# Ethernet.net
KiCad netlist of a schematic drawn in Altium Designer
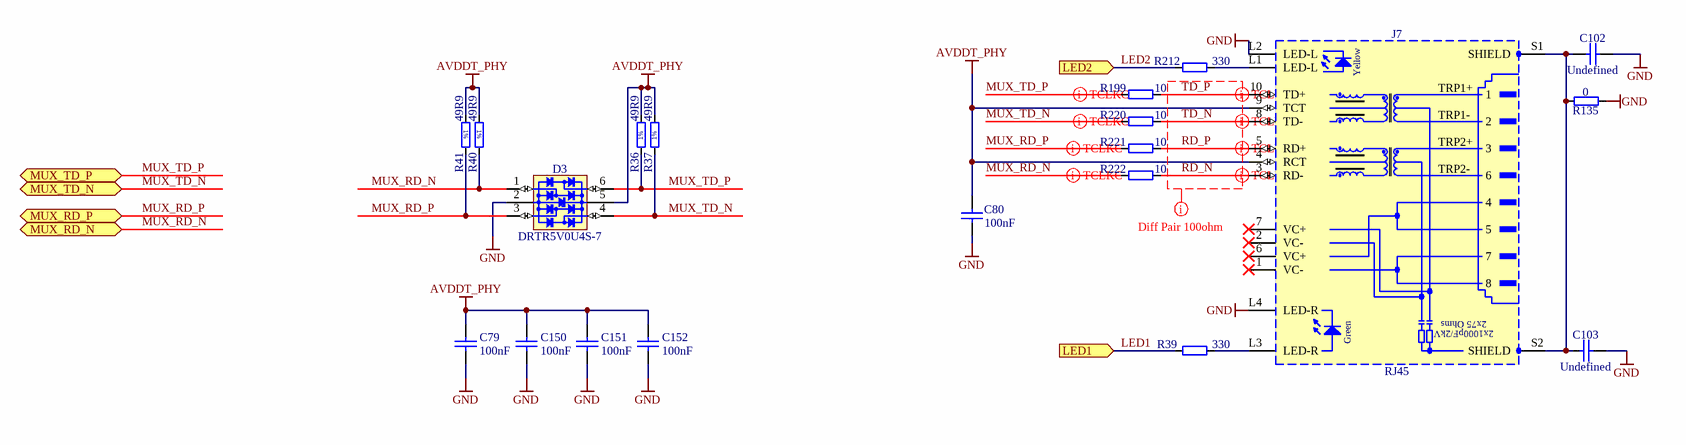
[diagram p0: Ethernet.SchDoc]

(export (version "E")
  (design (tool "Eeschema 10.0.6"))
  (components
    (comp (ref "C79")
      (value "100nF")
      (footprint "CAPC1005X55N")
      (description "Non-polarised capacitor")
      (fields
        (field (name "PART NUMBER") "CC0402_100NF_16V_10%_X5R")
        (field (name "VOLTAGE") "16V")
        (field (name "AUTHOR") "CERN DEM JLC")
      )
      (libsource (lib "Capacitors") (part "Capacitor - non polarized"))
    )
    (comp (ref "C80")
      (value "100nF")
      (footprint "CAPC1005X55N")
      (description "Non-polarised capacitor")
      (fields
        (field (name "PART NUMBER") "CC0402_100NF_16V_10%_X5R")
        (field (name "VOLTAGE") "16V")
        (field (name "AUTHOR") "CERN DEM JLC")
      )
      (libsource (lib "Capacitors") (part "Capacitor - non polarized"))
    )
    (comp (ref "C102")
      (value "Undefined")
      (footprint "CAPC2012X135N")
      (description "Non-polarised capacitor")
      (fields (field (name "PART NUMBER") "CC0805_NO-VALUE") (field (name "AUTHOR") "CERN DEM JLC"))
      (libsource (lib "Capacitors") (part "Capacitor - non polarized"))
    )
    (comp (ref "C103")
      (value "Undefined")
      (footprint "CAPC2012X135N")
      (description "Non-polarised capacitor")
      (fields (field (name "PART NUMBER") "CC0805_NO-VALUE") (field (name "AUTHOR") "CERN DEM JLC"))
      (libsource (lib "Capacitors") (part "Capacitor - non polarized"))
    )
    (comp (ref "C150")
      (value "100nF")
      (footprint "CAPC1005X55N")
      (description "Non-polarised capacitor")
      (fields
        (field (name "PART NUMBER") "CC0402_100NF_16V_10%_X5R")
        (field (name "VOLTAGE") "16V")
        (field (name "AUTHOR") "CERN DEM JLC")
      )
      (libsource (lib "Capacitors") (part "Capacitor - non polarized"))
    )
    (comp (ref "C151")
      (value "100nF")
      (footprint "CAPC1005X55N")
      (description "Non-polarised capacitor")
      (fields
        (field (name "PART NUMBER") "CC0402_100NF_16V_10%_X5R")
        (field (name "VOLTAGE") "16V")
        (field (name "AUTHOR") "CERN DEM JLC")
      )
      (libsource (lib "Capacitors") (part "Capacitor - non polarized"))
    )
    (comp (ref "C152")
      (value "100nF")
      (footprint "CAPC1005X55N")
      (description "Non-polarised capacitor")
      (fields
        (field (name "PART NUMBER") "CC0402_100NF_16V_10%_X5R")
        (field (name "VOLTAGE") "16V")
        (field (name "AUTHOR") "CERN DEM JLC")
      )
      (libsource (lib "Capacitors") (part "Capacitor - non polarized"))
    )
    (comp (ref "D3")
      (value "DRTR5V0U4S-7")
      (footprint "SOT65P210X110-6N")
      (description "Integrated Quad Ultra-Low Capacitance ESD Protection")
      (fields (field (name "MANUFACTURER") "DIODES") (field (name "AUTHOR") "GK"))
      (libsource (lib "Diodes") (part "D_TVS_DRTR5V0U4S-7"))
    )
    (comp (ref "J7")
      (value "RJ45")
      (footprint "ABRACON_ARJM11C7-114-BA-EW2")
      (description "MagJack 10/100BaseT, PoE+, 1X1, OG/Y, -40 to 85*C, Tab Up, RoHS")
      (fields
        (field (name "PART NUMBER") "ARJM11C7-114-BA-EW2")
        (field (name "MANUFACTURER") "Abracon")
        (field (name "AUTHOR") "GK")
      )
      (libsource (lib "LIBRARY_SCH") (part "CON_ETH_POE_ARJM11C7"))
    )
    (comp (ref "R36")
      (value "49R9")
      (footprint "RESC1005X40N")
      (description "Resistor - 1%")
      (fields
        (field (name "PART NUMBER") "R0402_49R9_1%_0.0625W_100PPM")
        (field (name "POWER") "0.0625W")
        (field (name "AUTHOR") "CERN DEM JLC")
      )
      (libsource (lib "Resistors") (part "Resistor - 1%"))
    )
    (comp (ref "R37")
      (value "49R9")
      (footprint "RESC1005X40N")
      (description "Resistor - 1%")
      (fields
        (field (name "PART NUMBER") "R0402_49R9_1%_0.0625W_100PPM")
        (field (name "POWER") "0.0625W")
        (field (name "AUTHOR") "CERN DEM JLC")
      )
      (libsource (lib "Resistors") (part "Resistor - 1%"))
    )
    (comp (ref "R39")
      (value "330")
      (footprint "RESC1005X40N")
      (description "Resistor - 1%")
      (fields
        (field (name "PART NUMBER") "R0402_330R_1%_0.0625W_100PPM")
        (field (name "POWER") "0.0625W")
        (field (name "AUTHOR") "CERN DEM JLC")
      )
      (libsource (lib "Resistors") (part "Resistor - 1%"))
    )
    (comp (ref "R40")
      (value "49R9")
      (footprint "RESC1005X40N")
      (description "Resistor - 1%")
      (fields
        (field (name "PART NUMBER") "R0402_49R9_1%_0.0625W_100PPM")
        (field (name "POWER") "0.0625W")
        (field (name "AUTHOR") "CERN DEM JLC")
      )
      (libsource (lib "Resistors") (part "Resistor - 1%"))
    )
    (comp (ref "R41")
      (value "49R9")
      (footprint "RESC1005X40N")
      (description "Resistor - 1%")
      (fields
        (field (name "PART NUMBER") "R0402_49R9_1%_0.0625W_100PPM")
        (field (name "POWER") "0.0625W")
        (field (name "AUTHOR") "CERN DEM JLC")
      )
      (libsource (lib "Resistors") (part "Resistor - 1%"))
    )
    (comp (ref "R135")
      (value "0")
      (footprint "RESC1608X55N")
      (description "Resistor")
      (fields
        (field (name "PART NUMBER") "R0603_0R_JUMPER")
        (field (name "MANUFACTURER") "GENERIC")
        (field (name "AUTHOR") "CERN DEM JLC")
      )
      (libsource (lib "Resistors") (part "Resistor"))
    )
    (comp (ref "R199")
      (value "10")
      (footprint "RESC1005X40N")
      (description "Resistor - 1%")
      (fields
        (field (name "PART NUMBER") "R0402_10R_1%_0.0625W_200PPM")
        (field (name "POWER") "0.0625W")
        (field (name "AUTHOR") "CERN DEM JLC")
      )
      (libsource (lib "Resistors") (part "Resistor - 1%"))
    )
    (comp (ref "R212")
      (value "330")
      (footprint "RESC1005X40N")
      (description "Resistor - 1%")
      (fields
        (field (name "PART NUMBER") "R0402_330R_1%_0.0625W_100PPM")
        (field (name "POWER") "0.0625W")
        (field (name "AUTHOR") "CERN DEM JLC")
      )
      (libsource (lib "Resistors") (part "Resistor - 1%"))
    )
    (comp (ref "R220")
      (value "10")
      (footprint "RESC1005X40N")
      (description "Resistor - 1%")
      (fields
        (field (name "PART NUMBER") "R0402_10R_1%_0.0625W_200PPM")
        (field (name "POWER") "0.0625W")
        (field (name "AUTHOR") "CERN DEM JLC")
      )
      (libsource (lib "Resistors") (part "Resistor - 1%"))
    )
    (comp (ref "R221")
      (value "10")
      (footprint "RESC1005X40N")
      (description "Resistor - 1%")
      (fields
        (field (name "PART NUMBER") "R0402_10R_1%_0.0625W_200PPM")
        (field (name "POWER") "0.0625W")
        (field (name "AUTHOR") "CERN DEM JLC")
      )
      (libsource (lib "Resistors") (part "Resistor - 1%"))
    )
    (comp (ref "R222")
      (value "10")
      (footprint "RESC1005X40N")
      (description "Resistor - 1%")
      (fields
        (field (name "PART NUMBER") "R0402_10R_1%_0.0625W_200PPM")
        (field (name "POWER") "0.0625W")
        (field (name "AUTHOR") "CERN DEM JLC")
      )
      (libsource (lib "Resistors") (part "Resistor - 1%"))
    )
  )
  (nets
    (net (code "1") (name "/LED1") (class "Default")
      (node (ref "R39") (pin "1") (pinfunction "1_1") (pintype "passive"))
    )
    (net (code "2") (name "/LED2") (class "Default")
      (node (ref "R212") (pin "1") (pinfunction "1_1") (pintype "passive"))
    )
    (net (code "3") (name "/MUX_RD_N") (class "Default")
      (node (ref "D3") (pin "1") (pinfunction "I/O1_1") (pintype "bidirectional"))
      (node (ref "R222") (pin "1") (pinfunction "1_1") (pintype "passive"))
      (node (ref "R40") (pin "2") (pinfunction "2_2") (pintype "passive"))
    )
    (net (code "4") (name "/MUX_RD_P") (class "Default")
      (node (ref "D3") (pin "3") (pinfunction "I/O2_3") (pintype "bidirectional"))
      (node (ref "R221") (pin "1") (pinfunction "1_1") (pintype "passive"))
      (node (ref "R41") (pin "2") (pinfunction "2_2") (pintype "passive"))
    )
    (net (code "5") (name "/MUX_TD_N") (class "Default")
      (node (ref "D3") (pin "4") (pinfunction "I/O3_4") (pintype "bidirectional"))
      (node (ref "R220") (pin "1") (pinfunction "1_1") (pintype "passive"))
      (node (ref "R37") (pin "1") (pinfunction "1_1") (pintype "passive"))
    )
    (net (code "6") (name "/MUX_TD_P") (class "Default")
      (node (ref "D3") (pin "6") (pinfunction "I/O4_6") (pintype "bidirectional"))
      (node (ref "R199") (pin "1") (pinfunction "1_1") (pintype "passive"))
      (node (ref "R36") (pin "1") (pinfunction "1_1") (pintype "passive"))
    )
    (net (code "7") (name "/RD_N") (class "Default")
      (node (ref "J7") (pin "3") (pinfunction "RD-_3") (pintype "bidirectional"))
      (node (ref "R222") (pin "2") (pinfunction "2_2") (pintype "passive"))
    )
    (net (code "8") (name "/RD_P") (class "Default")
      (node (ref "J7") (pin "5") (pinfunction "RD+_5") (pintype "bidirectional"))
      (node (ref "R221") (pin "2") (pinfunction "2_2") (pintype "passive"))
    )
    (net (code "9") (name "/TD_N") (class "Default")
      (node (ref "J7") (pin "8") (pinfunction "TD-_8") (pintype "bidirectional"))
      (node (ref "R220") (pin "2") (pinfunction "2_2") (pintype "passive"))
    )
    (net (code "10") (name "/TD_P") (class "Default")
      (node (ref "J7") (pin "10") (pinfunction "TD+_10") (pintype "bidirectional"))
      (node (ref "R199") (pin "2") (pinfunction "2_2") (pintype "passive"))
    )
    (net (code "11") (name "AVDDT_PHY") (class "Default")
      (node (ref "C150") (pin "1") (pinfunction "1_1") (pintype "passive"))
      (node (ref "C151") (pin "1") (pinfunction "1_1") (pintype "passive"))
      (node (ref "C152") (pin "1") (pinfunction "1_1") (pintype "passive"))
      (node (ref "C79") (pin "1") (pinfunction "1_1") (pintype "passive"))
      (node (ref "C80") (pin "2") (pinfunction "2_2") (pintype "passive"))
      (node (ref "D3") (pin "5") (pinfunction "VBUS_5") (pintype "power_in"))
      (node (ref "J7") (pin "4") (pinfunction "RCT_4") (pintype "bidirectional"))
      (node (ref "J7") (pin "9") (pinfunction "TCT_9") (pintype "bidirectional"))
      (node (ref "R36") (pin "2") (pinfunction "2_2") (pintype "passive"))
      (node (ref "R37") (pin "2") (pinfunction "2_2") (pintype "passive"))
      (node (ref "R40") (pin "1") (pinfunction "1_1") (pintype "passive"))
      (node (ref "R41") (pin "1") (pinfunction "1_1") (pintype "passive"))
    )
    (net (code "12") (name "GND") (class "Default")
      (node (ref "C102") (pin "2") (pinfunction "2_2") (pintype "passive"))
      (node (ref "C103") (pin "2") (pinfunction "2_2") (pintype "passive"))
      (node (ref "C150") (pin "2") (pinfunction "2_2") (pintype "passive"))
      (node (ref "C151") (pin "2") (pinfunction "2_2") (pintype "passive"))
      (node (ref "C152") (pin "2") (pinfunction "2_2") (pintype "passive"))
      (node (ref "C79") (pin "2") (pinfunction "2_2") (pintype "passive"))
      (node (ref "C80") (pin "1") (pinfunction "1_1") (pintype "passive"))
      (node (ref "D3") (pin "2") (pinfunction "GND_2") (pintype "power_in"))
      (node (ref "J7") (pin "L2") (pinfunction "LED-L_L2") (pintype "passive"))
      (node (ref "J7") (pin "L4") (pinfunction "LED-R_L4") (pintype "passive"))
      (node (ref "R135") (pin "1") (pinfunction "1_1") (pintype "passive"))
    )
    (net (code "13") (name "Net-(C102-Pad1)") (class "Default")
      (node (ref "C102") (pin "1") (pinfunction "1_1") (pintype "passive"))
      (node (ref "C103") (pin "1") (pinfunction "1_1") (pintype "passive"))
      (node (ref "J7") (pin "S1") (pinfunction "SHIELD_S1") (pintype "power_in"))
      (node (ref "J7") (pin "S2") (pinfunction "SHIELD_S2") (pintype "power_in"))
      (node (ref "R135") (pin "2") (pinfunction "2_2") (pintype "passive"))
    )
    (net (code "14") (name "Net-(J7-LED-L-PadL1)") (class "Default")
      (node (ref "J7") (pin "L1") (pinfunction "LED-L_L1") (pintype "passive"))
      (node (ref "R212") (pin "2") (pinfunction "2_2") (pintype "passive"))
    )
    (net (code "15") (name "Net-(J7-LED-R-PadL3)") (class "Default")
      (node (ref "J7") (pin "L3") (pinfunction "LED-R_L3") (pintype "passive"))
      (node (ref "R39") (pin "2") (pinfunction "2_2") (pintype "passive"))
    )
    (net (code "16") (name "unconnected-(J7-VC+-Pad6)") (class "Default")
      (node (ref "J7") (pin "6") (pinfunction "VC+_6") (pintype "passive+no_connect"))
    )
    (net (code "17") (name "unconnected-(J7-VC+-Pad7)") (class "Default")
      (node (ref "J7") (pin "7") (pinfunction "VC+_7") (pintype "passive+no_connect"))
    )
    (net (code "18") (name "unconnected-(J7-VC--Pad1)") (class "Default")
      (node (ref "J7") (pin "1") (pinfunction "VC-_1") (pintype "passive+no_connect"))
    )
    (net (code "19") (name "unconnected-(J7-VC--Pad2)") (class "Default")
      (node (ref "J7") (pin "2") (pinfunction "VC-_2") (pintype "passive+no_connect"))
    )
  )
)
